# FPGA_MEMORIES.net
KiCad netlist of a schematic drawn in Altium Designer
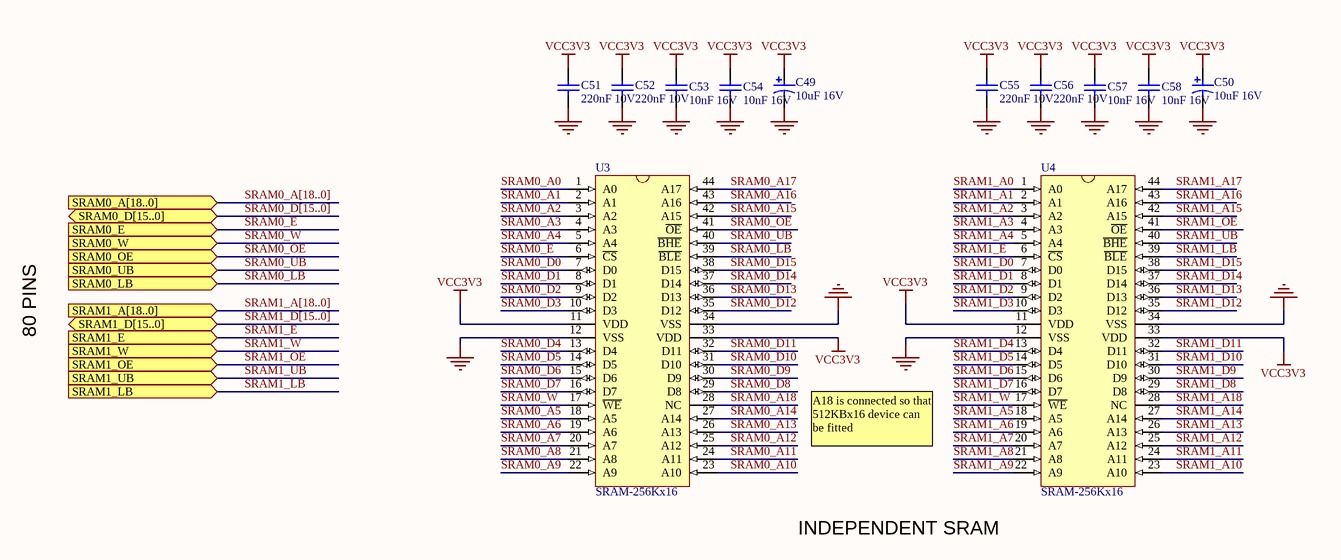
[diagram p0: FPGA_MEMORIES.SCHDOC]

(export (version "E")
  (design (tool "Eeschema 10.0.6"))
  (components
    (comp (ref "C49")
      (value "10uF 16V")
      (footprint "CAPC3528")
      (description "Polar Capacitor")
      (libsource (lib "Altium Design Library") (part "CAP-P"))
    )
    (comp (ref "C50")
      (value "10uF 16V")
      (footprint "CAPC3528")
      (description "Polar Capacitor")
      (libsource (lib "Altium Design Library") (part "CAP-P"))
    )
    (comp (ref "C51")
      (value "220nF 10V")
      (footprint "CAPC1608")
      (description "Capacitor")
      (libsource (lib "Altium Design Library") (part "CAP-NP"))
    )
    (comp (ref "C52")
      (value "220nF 10V")
      (footprint "CAPC1608")
      (description "Capacitor")
      (libsource (lib "Altium Design Library") (part "CAP-NP"))
    )
    (comp (ref "C53")
      (value "10nF 16V")
      (footprint "CAPC1005")
      (description "Capacitor")
      (libsource (lib "Altium Design Library") (part "CAP-NP"))
    )
    (comp (ref "C54")
      (value "10nF 16V")
      (footprint "CAPC1005")
      (description "Capacitor")
      (libsource (lib "Altium Design Library") (part "CAP-NP"))
    )
    (comp (ref "C55")
      (value "220nF 10V")
      (footprint "CAPC1608")
      (description "Capacitor")
      (libsource (lib "Altium Design Library") (part "CAP-NP"))
    )
    (comp (ref "C56")
      (value "220nF 10V")
      (footprint "CAPC1608")
      (description "Capacitor")
      (libsource (lib "Altium Design Library") (part "CAP-NP"))
    )
    (comp (ref "C57")
      (value "10nF 16V")
      (footprint "CAPC1005")
      (description "Capacitor")
      (libsource (lib "Altium Design Library") (part "CAP-NP"))
    )
    (comp (ref "C58")
      (value "10nF 16V")
      (footprint "CAPC1005")
      (description "Capacitor")
      (libsource (lib "Altium Design Library") (part "CAP-NP"))
    )
    (comp (ref "U3")
      (value "SRAM-256Kx16")
      (footprint "TSOP80P1176-44")
      (description "256Kx16Bit SRAM TSOP44")
      (libsource (lib "Altium Design Library") (part "K6R4016V1D-T"))
    )
    (comp (ref "U4")
      (value "SRAM-256Kx16")
      (footprint "TSOP80P1176-44")
      (description "256Kx16Bit SRAM TSOP44")
      (libsource (lib "Altium Design Library") (part "K6R4016V1D-T"))
    )
  )
  (nets
    (net (code "1") (name "/SRAM0_A0") (class "Default")
      (node (ref "U3") (pin "1") (pinfunction "A0_1") (pintype "input"))
    )
    (net (code "2") (name "/SRAM0_A1") (class "Default")
      (node (ref "U3") (pin "2") (pinfunction "A1_2") (pintype "input"))
    )
    (net (code "3") (name "/SRAM0_A2") (class "Default")
      (node (ref "U3") (pin "3") (pinfunction "A2_3") (pintype "input"))
    )
    (net (code "4") (name "/SRAM0_A3") (class "Default")
      (node (ref "U3") (pin "4") (pinfunction "A3_4") (pintype "input"))
    )
    (net (code "5") (name "/SRAM0_A4") (class "Default")
      (node (ref "U3") (pin "5") (pinfunction "A4_5") (pintype "input"))
    )
    (net (code "6") (name "/SRAM0_A5") (class "Default")
      (node (ref "U3") (pin "18") (pinfunction "A5_18") (pintype "input"))
    )
    (net (code "7") (name "/SRAM0_A6") (class "Default")
      (node (ref "U3") (pin "19") (pinfunction "A6_19") (pintype "input"))
    )
    (net (code "8") (name "/SRAM0_A7") (class "Default")
      (node (ref "U3") (pin "20") (pinfunction "A7_20") (pintype "input"))
    )
    (net (code "9") (name "/SRAM0_A8") (class "Default")
      (node (ref "U3") (pin "21") (pinfunction "A8_21") (pintype "input"))
    )
    (net (code "10") (name "/SRAM0_A9") (class "Default")
      (node (ref "U3") (pin "22") (pinfunction "A9_22") (pintype "input"))
    )
    (net (code "11") (name "/SRAM0_A10") (class "Default")
      (node (ref "U3") (pin "23") (pinfunction "A10_23") (pintype "input"))
    )
    (net (code "12") (name "/SRAM0_A11") (class "Default")
      (node (ref "U3") (pin "24") (pinfunction "A11_24") (pintype "input"))
    )
    (net (code "13") (name "/SRAM0_A12") (class "Default")
      (node (ref "U3") (pin "25") (pinfunction "A12_25") (pintype "input"))
    )
    (net (code "14") (name "/SRAM0_A13") (class "Default")
      (node (ref "U3") (pin "26") (pinfunction "A13_26") (pintype "input"))
    )
    (net (code "15") (name "/SRAM0_A14") (class "Default")
      (node (ref "U3") (pin "27") (pinfunction "A14_27") (pintype "input"))
    )
    (net (code "16") (name "/SRAM0_A15") (class "Default")
      (node (ref "U3") (pin "42") (pinfunction "A15_42") (pintype "input"))
    )
    (net (code "17") (name "/SRAM0_A16") (class "Default")
      (node (ref "U3") (pin "43") (pinfunction "A16_43") (pintype "input"))
    )
    (net (code "18") (name "/SRAM0_A17") (class "Default")
      (node (ref "U3") (pin "44") (pinfunction "A17_44") (pintype "input"))
    )
    (net (code "19") (name "/SRAM0_A18") (class "Default")
      (node (ref "U3") (pin "28") (pinfunction "NC_28") (pintype "passive"))
    )
    (net (code "21") (name "/SRAM0_D0") (class "Default")
      (node (ref "U3") (pin "7") (pinfunction "D0_7") (pintype "bidirectional"))
    )
    (net (code "22") (name "/SRAM0_D1") (class "Default")
      (node (ref "U3") (pin "8") (pinfunction "D1_8") (pintype "bidirectional"))
    )
    (net (code "23") (name "/SRAM0_D2") (class "Default")
      (node (ref "U3") (pin "9") (pinfunction "D2_9") (pintype "bidirectional"))
    )
    (net (code "24") (name "/SRAM0_D3") (class "Default")
      (node (ref "U3") (pin "10") (pinfunction "D3_10") (pintype "bidirectional"))
    )
    (net (code "25") (name "/SRAM0_D4") (class "Default")
      (node (ref "U3") (pin "13") (pinfunction "D4_13") (pintype "bidirectional"))
    )
    (net (code "26") (name "/SRAM0_D5") (class "Default")
      (node (ref "U3") (pin "14") (pinfunction "D5_14") (pintype "bidirectional"))
    )
    (net (code "27") (name "/SRAM0_D6") (class "Default")
      (node (ref "U3") (pin "15") (pinfunction "D6_15") (pintype "bidirectional"))
    )
    (net (code "28") (name "/SRAM0_D7") (class "Default")
      (node (ref "U3") (pin "16") (pinfunction "D7_16") (pintype "bidirectional"))
    )
    (net (code "29") (name "/SRAM0_D8") (class "Default")
      (node (ref "U3") (pin "29") (pinfunction "D8_29") (pintype "bidirectional"))
    )
    (net (code "30") (name "/SRAM0_D9") (class "Default")
      (node (ref "U3") (pin "30") (pinfunction "D9_30") (pintype "bidirectional"))
    )
    (net (code "31") (name "/SRAM0_D10") (class "Default")
      (node (ref "U3") (pin "31") (pinfunction "D10_31") (pintype "bidirectional"))
    )
    (net (code "32") (name "/SRAM0_D11") (class "Default")
      (node (ref "U3") (pin "32") (pinfunction "D11_32") (pintype "bidirectional"))
    )
    (net (code "33") (name "/SRAM0_D12") (class "Default")
      (node (ref "U3") (pin "35") (pinfunction "D12_35") (pintype "bidirectional"))
    )
    (net (code "34") (name "/SRAM0_D13") (class "Default")
      (node (ref "U3") (pin "36") (pinfunction "D13_36") (pintype "bidirectional"))
    )
    (net (code "35") (name "/SRAM0_D14") (class "Default")
      (node (ref "U3") (pin "37") (pinfunction "D14_37") (pintype "bidirectional"))
    )
    (net (code "36") (name "/SRAM0_D15") (class "Default")
      (node (ref "U3") (pin "38") (pinfunction "D15_38") (pintype "bidirectional"))
    )
    (net (code "38") (name "/SRAM0_E") (class "Default")
      (node (ref "U3") (pin "6") (pinfunction "~{CS}_6") (pintype "input"))
    )
    (net (code "39") (name "/SRAM0_LB") (class "Default")
      (node (ref "U3") (pin "39") (pinfunction "~{BLE}_39") (pintype "input"))
    )
    (net (code "40") (name "/SRAM0_OE") (class "Default")
      (node (ref "U3") (pin "41") (pinfunction "~{OE}_41") (pintype "input"))
    )
    (net (code "41") (name "/SRAM0_UB") (class "Default")
      (node (ref "U3") (pin "40") (pinfunction "~{BHE}_40") (pintype "input"))
    )
    (net (code "42") (name "/SRAM0_W") (class "Default")
      (node (ref "U3") (pin "17") (pinfunction "~{WE}_17") (pintype "input"))
    )
    (net (code "43") (name "/SRAM1_A0") (class "Default")
      (node (ref "U4") (pin "1") (pinfunction "A0_1") (pintype "input"))
    )
    (net (code "44") (name "/SRAM1_A1") (class "Default")
      (node (ref "U4") (pin "2") (pinfunction "A1_2") (pintype "input"))
    )
    (net (code "45") (name "/SRAM1_A2") (class "Default")
      (node (ref "U4") (pin "3") (pinfunction "A2_3") (pintype "input"))
    )
    (net (code "46") (name "/SRAM1_A3") (class "Default")
      (node (ref "U4") (pin "4") (pinfunction "A3_4") (pintype "input"))
    )
    (net (code "47") (name "/SRAM1_A4") (class "Default")
      (node (ref "U4") (pin "5") (pinfunction "A4_5") (pintype "input"))
    )
    (net (code "48") (name "/SRAM1_A5") (class "Default")
      (node (ref "U4") (pin "18") (pinfunction "A5_18") (pintype "input"))
    )
    (net (code "49") (name "/SRAM1_A6") (class "Default")
      (node (ref "U4") (pin "19") (pinfunction "A6_19") (pintype "input"))
    )
    (net (code "50") (name "/SRAM1_A7") (class "Default")
      (node (ref "U4") (pin "20") (pinfunction "A7_20") (pintype "input"))
    )
    (net (code "51") (name "/SRAM1_A8") (class "Default")
      (node (ref "U4") (pin "21") (pinfunction "A8_21") (pintype "input"))
    )
    (net (code "52") (name "/SRAM1_A9") (class "Default")
      (node (ref "U4") (pin "22") (pinfunction "A9_22") (pintype "input"))
    )
    (net (code "53") (name "/SRAM1_A10") (class "Default")
      (node (ref "U4") (pin "23") (pinfunction "A10_23") (pintype "input"))
    )
    (net (code "54") (name "/SRAM1_A11") (class "Default")
      (node (ref "U4") (pin "24") (pinfunction "A11_24") (pintype "input"))
    )
    (net (code "55") (name "/SRAM1_A12") (class "Default")
      (node (ref "U4") (pin "25") (pinfunction "A12_25") (pintype "input"))
    )
    (net (code "56") (name "/SRAM1_A13") (class "Default")
      (node (ref "U4") (pin "26") (pinfunction "A13_26") (pintype "input"))
    )
    (net (code "57") (name "/SRAM1_A14") (class "Default")
      (node (ref "U4") (pin "27") (pinfunction "A14_27") (pintype "input"))
    )
    (net (code "58") (name "/SRAM1_A15") (class "Default")
      (node (ref "U4") (pin "42") (pinfunction "A15_42") (pintype "input"))
    )
    (net (code "59") (name "/SRAM1_A16") (class "Default")
      (node (ref "U4") (pin "43") (pinfunction "A16_43") (pintype "input"))
    )
    (net (code "60") (name "/SRAM1_A17") (class "Default")
      (node (ref "U4") (pin "44") (pinfunction "A17_44") (pintype "input"))
    )
    (net (code "61") (name "/SRAM1_A18") (class "Default")
      (node (ref "U4") (pin "28") (pinfunction "NC_28") (pintype "passive"))
    )
    (net (code "63") (name "/SRAM1_D0") (class "Default")
      (node (ref "U4") (pin "7") (pinfunction "D0_7") (pintype "bidirectional"))
    )
    (net (code "64") (name "/SRAM1_D1") (class "Default")
      (node (ref "U4") (pin "8") (pinfunction "D1_8") (pintype "bidirectional"))
    )
    (net (code "65") (name "/SRAM1_D2") (class "Default")
      (node (ref "U4") (pin "9") (pinfunction "D2_9") (pintype "bidirectional"))
    )
    (net (code "66") (name "/SRAM1_D3") (class "Default")
      (node (ref "U4") (pin "10") (pinfunction "D3_10") (pintype "bidirectional"))
    )
    (net (code "67") (name "/SRAM1_D4") (class "Default")
      (node (ref "U4") (pin "13") (pinfunction "D4_13") (pintype "bidirectional"))
    )
    (net (code "68") (name "/SRAM1_D5") (class "Default")
      (node (ref "U4") (pin "14") (pinfunction "D5_14") (pintype "bidirectional"))
    )
    (net (code "69") (name "/SRAM1_D6") (class "Default")
      (node (ref "U4") (pin "15") (pinfunction "D6_15") (pintype "bidirectional"))
    )
    (net (code "70") (name "/SRAM1_D7") (class "Default")
      (node (ref "U4") (pin "16") (pinfunction "D7_16") (pintype "bidirectional"))
    )
    (net (code "71") (name "/SRAM1_D8") (class "Default")
      (node (ref "U4") (pin "29") (pinfunction "D8_29") (pintype "bidirectional"))
    )
    (net (code "72") (name "/SRAM1_D9") (class "Default")
      (node (ref "U4") (pin "30") (pinfunction "D9_30") (pintype "bidirectional"))
    )
    (net (code "73") (name "/SRAM1_D10") (class "Default")
      (node (ref "U4") (pin "31") (pinfunction "D10_31") (pintype "bidirectional"))
    )
    (net (code "74") (name "/SRAM1_D11") (class "Default")
      (node (ref "U4") (pin "32") (pinfunction "D11_32") (pintype "bidirectional"))
    )
    (net (code "75") (name "/SRAM1_D12") (class "Default")
      (node (ref "U4") (pin "35") (pinfunction "D12_35") (pintype "bidirectional"))
    )
    (net (code "76") (name "/SRAM1_D13") (class "Default")
      (node (ref "U4") (pin "36") (pinfunction "D13_36") (pintype "bidirectional"))
    )
    (net (code "77") (name "/SRAM1_D14") (class "Default")
      (node (ref "U4") (pin "37") (pinfunction "D14_37") (pintype "bidirectional"))
    )
    (net (code "78") (name "/SRAM1_D15") (class "Default")
      (node (ref "U4") (pin "38") (pinfunction "D15_38") (pintype "bidirectional"))
    )
    (net (code "80") (name "/SRAM1_E") (class "Default")
      (node (ref "U4") (pin "6") (pinfunction "~{CS}_6") (pintype "input"))
    )
    (net (code "81") (name "/SRAM1_LB") (class "Default")
      (node (ref "U4") (pin "39") (pinfunction "~{BLE}_39") (pintype "input"))
    )
    (net (code "82") (name "/SRAM1_OE") (class "Default")
      (node (ref "U4") (pin "41") (pinfunction "~{OE}_41") (pintype "input"))
    )
    (net (code "83") (name "/SRAM1_UB") (class "Default")
      (node (ref "U4") (pin "40") (pinfunction "~{BHE}_40") (pintype "input"))
    )
    (net (code "84") (name "/SRAM1_W") (class "Default")
      (node (ref "U4") (pin "17") (pinfunction "~{WE}_17") (pintype "input"))
    )
    (net (code "85") (name "GND") (class "Default")
      (node (ref "C49") (pin "2") (pinfunction "2_2") (pintype "passive"))
      (node (ref "C50") (pin "2") (pinfunction "2_2") (pintype "passive"))
      (node (ref "C51") (pin "2") (pinfunction "2_2") (pintype "passive"))
      (node (ref "C52") (pin "2") (pinfunction "2_2") (pintype "passive"))
      (node (ref "C53") (pin "2") (pinfunction "2_2") (pintype "passive"))
      (node (ref "C54") (pin "2") (pinfunction "2_2") (pintype "passive"))
      (node (ref "C55") (pin "2") (pinfunction "2_2") (pintype "passive"))
      (node (ref "C56") (pin "2") (pinfunction "2_2") (pintype "passive"))
      (node (ref "C57") (pin "2") (pinfunction "2_2") (pintype "passive"))
      (node (ref "C58") (pin "2") (pinfunction "2_2") (pintype "passive"))
      (node (ref "U3") (pin "12") (pinfunction "VSS_12") (pintype "power_in"))
      (node (ref "U3") (pin "34") (pinfunction "VSS_34") (pintype "power_in"))
      (node (ref "U4") (pin "12") (pinfunction "VSS_12") (pintype "power_in"))
      (node (ref "U4") (pin "34") (pinfunction "VSS_34") (pintype "power_in"))
    )
    (net (code "86") (name "VCC3V3") (class "Default")
      (node (ref "C49") (pin "1") (pinfunction "1_1") (pintype "passive"))
      (node (ref "C50") (pin "1") (pinfunction "1_1") (pintype "passive"))
      (node (ref "C51") (pin "1") (pinfunction "1_1") (pintype "passive"))
      (node (ref "C52") (pin "1") (pinfunction "1_1") (pintype "passive"))
      (node (ref "C53") (pin "1") (pinfunction "1_1") (pintype "passive"))
      (node (ref "C54") (pin "1") (pinfunction "1_1") (pintype "passive"))
      (node (ref "C55") (pin "1") (pinfunction "1_1") (pintype "passive"))
      (node (ref "C56") (pin "1") (pinfunction "1_1") (pintype "passive"))
      (node (ref "C57") (pin "1") (pinfunction "1_1") (pintype "passive"))
      (node (ref "C58") (pin "1") (pinfunction "1_1") (pintype "passive"))
      (node (ref "U3") (pin "11") (pinfunction "VDD_11") (pintype "power_in"))
      (node (ref "U3") (pin "33") (pinfunction "VDD_33") (pintype "power_in"))
      (node (ref "U4") (pin "11") (pinfunction "VDD_11") (pintype "power_in"))
      (node (ref "U4") (pin "33") (pinfunction "VDD_33") (pintype "power_in"))
    )
  )
)
